# ei2c.net
KiCad netlist of a schematic drawn in EAGLE
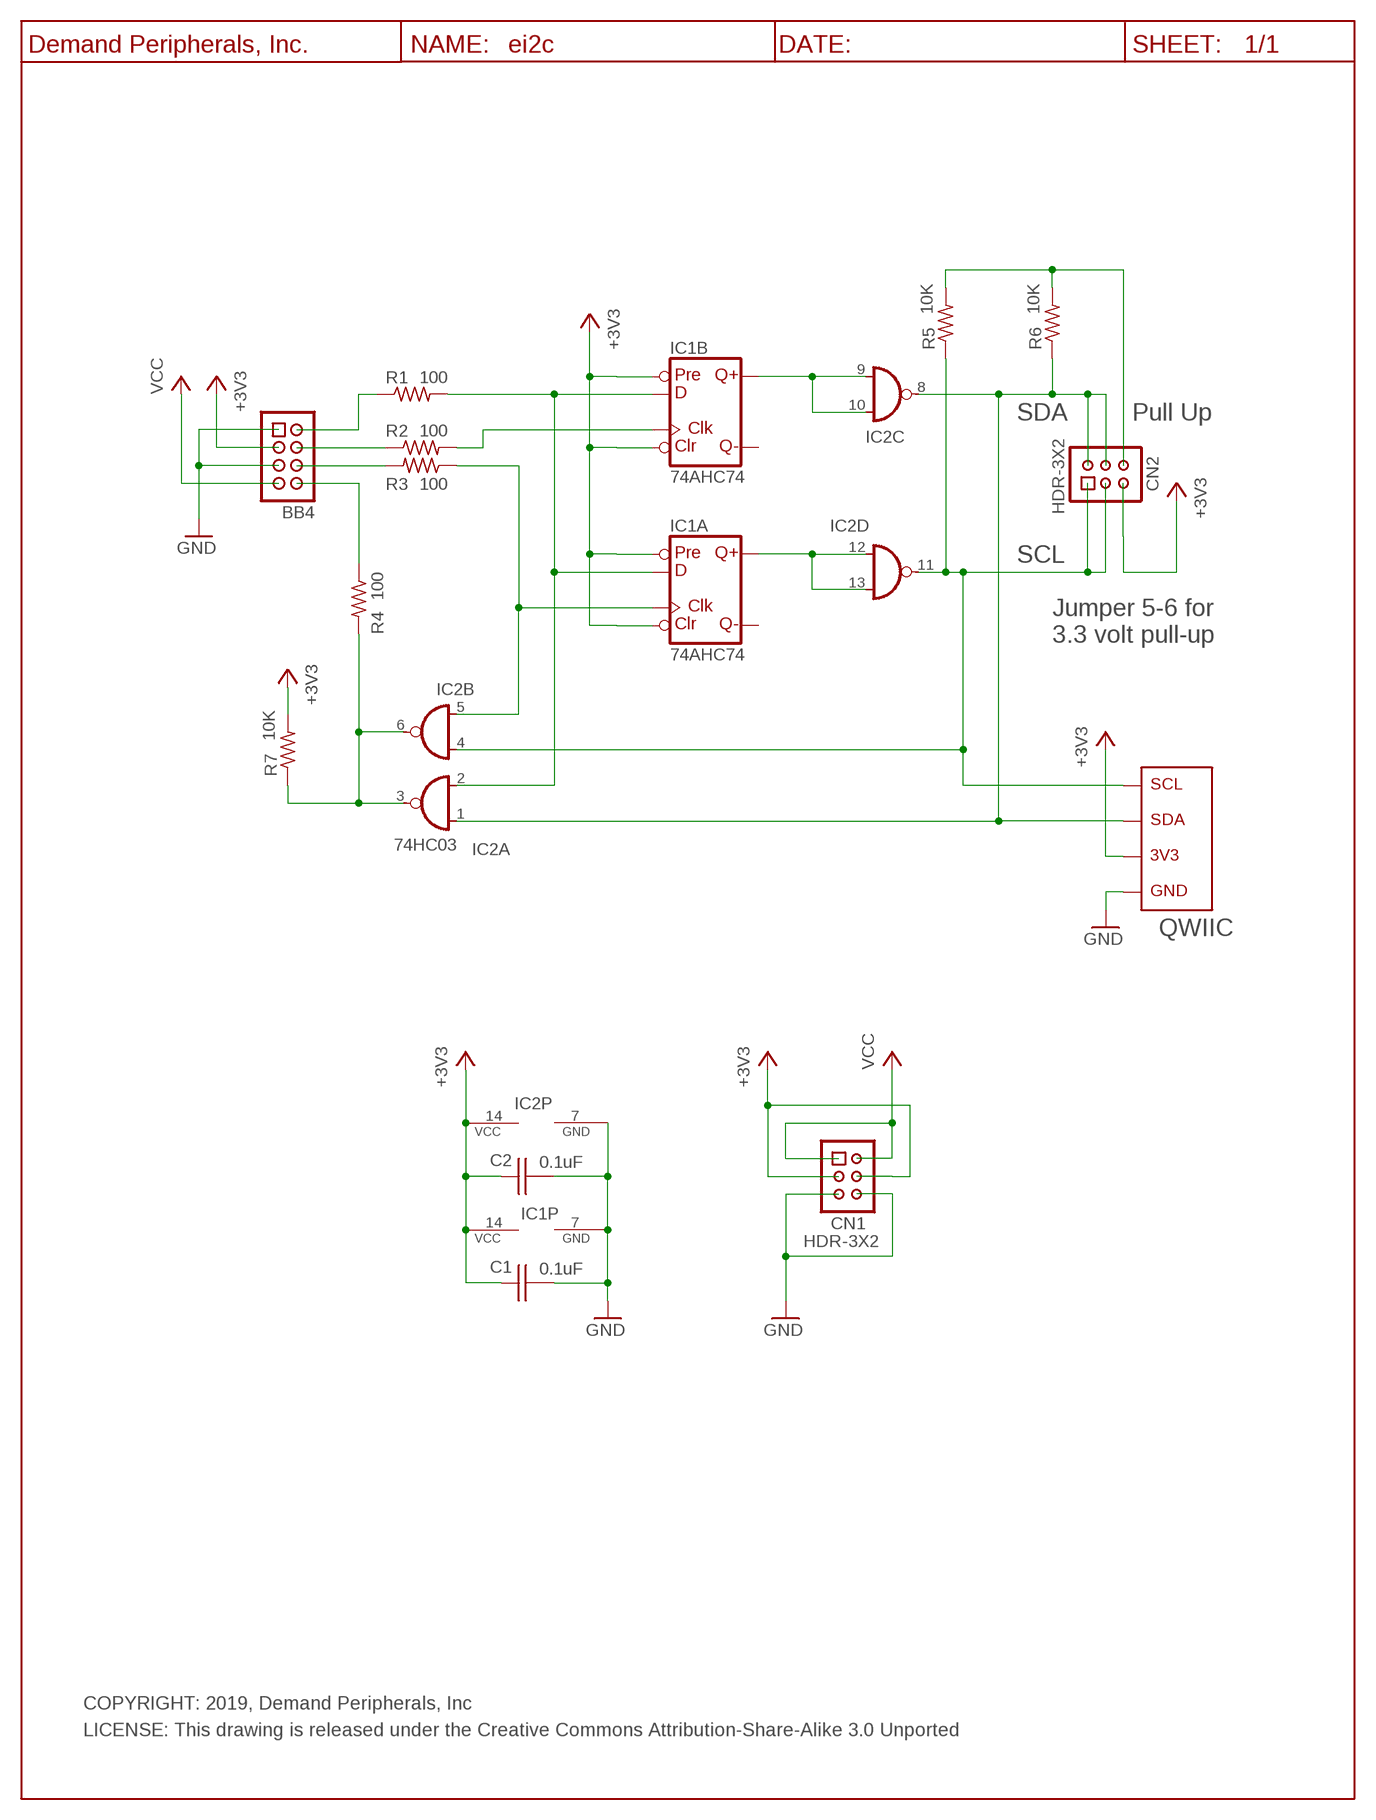
[diagram p0: schematic, sheet 1]

(export (version "E")
  (design (tool "Eeschema 10.0.6"))
  (components
    (comp (ref "BB4")
      (value "BB_CON")
      (footprint "eagle-import:HDR-4X2")
      (libsource (lib "eagle-import") (part "HDR-4X2-SHR"))
    )
    (comp (ref "C1")
      (value "0.1uF")
      (footprint "eagle-import:C0603")
      (libsource (lib "eagle-import") (part "C0.1UF_C0603"))
    )
    (comp (ref "C2")
      (value "0.1uF")
      (footprint "eagle-import:C0603")
      (libsource (lib "eagle-import") (part "C0.1UF_C0603"))
    )
    (comp (ref "CN1")
      (value "HDR-3X2")
      (footprint "eagle-import:HDR-3X2")
      (libsource (lib "eagle-import") (part "HDR-3X2"))
    )
    (comp (ref "CN2")
      (value "HDR-3X2")
      (footprint "eagle-import:HDR-3X2")
      (libsource (lib "eagle-import") (part "HDR-3X2"))
    )
    (comp (ref "IC1")
      (value "74AHC74")
      (footprint "eagle-import:SO14")
      (libsource (lib "eagle-import") (part "74AHC74SS"))
    )
    (comp (ref "IC2")
      (value "74HC03")
      (footprint "eagle-import:SO14")
      (libsource (lib "eagle-import") (part "7403HC"))
    )
    (comp (ref "QWIIC")
      (value "QWIIC-VCN")
      (footprint "eagle-import:QWIIC")
      (libsource (lib "eagle-import") (part "QWIIC-VCN"))
    )
    (comp (ref "R1")
      (value "100")
      (footprint "eagle-import:R0603")
      (libsource (lib "eagle-import") (part "R100_R0603"))
    )
    (comp (ref "R2")
      (value "100")
      (footprint "eagle-import:R0603")
      (libsource (lib "eagle-import") (part "R100_R0603"))
    )
    (comp (ref "R3")
      (value "100")
      (footprint "eagle-import:R0603")
      (libsource (lib "eagle-import") (part "R100_R0603"))
    )
    (comp (ref "R4")
      (value "100")
      (footprint "eagle-import:R0603")
      (libsource (lib "eagle-import") (part "R100_R0603"))
    )
    (comp (ref "R5")
      (value "10K")
      (footprint "eagle-import:R0603")
      (libsource (lib "eagle-import") (part "R10K_R0603"))
    )
    (comp (ref "R6")
      (value "10K")
      (footprint "eagle-import:R0603")
      (libsource (lib "eagle-import") (part "R10K_R0603"))
    )
    (comp (ref "R7")
      (value "10K")
      (footprint "eagle-import:R0603")
      (libsource (lib "eagle-import") (part "R10K_R0603"))
    )
    (comp (ref "U$3")
      (value "DP_FRAME_P")
      (footprint "eagle-import:P_FRAME")
      (libsource (lib "eagle-import") (part "DP_FRAME_P"))
    )
  )
  (nets
    (net (code "1") (name "+3V3") (class "Default")
      (node (ref "BB4") (pin "3") (pinfunction "3_3") (pintype "passive"))
      (node (ref "C1") (pin "1") (pinfunction "1_1") (pintype "passive"))
      (node (ref "C2") (pin "1") (pinfunction "1_1") (pintype "passive"))
      (node (ref "CN1") (pin "3") (pinfunction "3_3") (pintype "passive"))
      (node (ref "CN1") (pin "4") (pinfunction "4_4") (pintype "passive"))
      (node (ref "CN2") (pin "5") (pinfunction "5_5") (pintype "passive"))
      (node (ref "IC1") (pin "1") (pinfunction "CLR_1") (pintype "input"))
      (node (ref "IC1") (pin "10") (pinfunction "PRE_10") (pintype "input"))
      (node (ref "IC1") (pin "13") (pinfunction "CLR_13") (pintype "input"))
      (node (ref "IC1") (pin "14") (pinfunction "VCC_14") (pintype "power_in"))
      (node (ref "IC1") (pin "4") (pinfunction "PRE_4") (pintype "input"))
      (node (ref "IC2") (pin "14") (pinfunction "VCC_14") (pintype "power_in"))
      (node (ref "QWIIC") (pin "2") (pinfunction "2_2") (pintype "passive"))
      (node (ref "R7") (pin "2") (pinfunction "2_2") (pintype "passive"))
    )
    (net (code "2") (name "GND") (class "Default")
      (node (ref "BB4") (pin "1") (pinfunction "1_1") (pintype "passive"))
      (node (ref "BB4") (pin "5") (pinfunction "5_5") (pintype "passive"))
      (node (ref "C1") (pin "2") (pinfunction "2_2") (pintype "passive"))
      (node (ref "C2") (pin "2") (pinfunction "2_2") (pintype "passive"))
      (node (ref "CN1") (pin "5") (pinfunction "5_5") (pintype "passive"))
      (node (ref "CN1") (pin "6") (pinfunction "6_6") (pintype "passive"))
      (node (ref "IC1") (pin "7") (pinfunction "GND_7") (pintype "power_in"))
      (node (ref "IC2") (pin "7") (pinfunction "GND_7") (pintype "power_in"))
      (node (ref "QWIIC") (pin "1") (pinfunction "1_1") (pintype "passive"))
    )
    (net (code "3") (name "Net-(BB4-Pad2)") (class "Default")
      (node (ref "BB4") (pin "2") (pinfunction "2_2") (pintype "passive"))
      (node (ref "R1") (pin "1") (pinfunction "1_1") (pintype "passive"))
    )
    (net (code "4") (name "Net-(BB4-Pad4)") (class "Default")
      (node (ref "BB4") (pin "4") (pinfunction "4_4") (pintype "passive"))
      (node (ref "R2") (pin "1") (pinfunction "1_1") (pintype "passive"))
    )
    (net (code "5") (name "Net-(BB4-Pad6)") (class "Default")
      (node (ref "BB4") (pin "6") (pinfunction "6_6") (pintype "passive"))
      (node (ref "R3") (pin "2") (pinfunction "2_2") (pintype "passive"))
    )
    (net (code "6") (name "Net-(BB4-Pad8)") (class "Default")
      (node (ref "BB4") (pin "8") (pinfunction "8_8") (pintype "passive"))
      (node (ref "R4") (pin "1") (pinfunction "1_1") (pintype "passive"))
    )
    (net (code "7") (name "Net-(CN2-Pad6)") (class "Default")
      (node (ref "CN2") (pin "6") (pinfunction "6_6") (pintype "passive"))
      (node (ref "R5") (pin "2") (pinfunction "2_2") (pintype "passive"))
      (node (ref "R6") (pin "2") (pinfunction "2_2") (pintype "passive"))
    )
    (net (code "8") (name "Net-(IC1A-CLK)") (class "Default")
      (node (ref "IC1") (pin "3") (pinfunction "CLK_3") (pintype "input"))
      (node (ref "IC2") (pin "5") (pinfunction "I1_5") (pintype "input"))
      (node (ref "R3") (pin "1") (pinfunction "1_1") (pintype "passive"))
    )
    (net (code "9") (name "Net-(IC1A-D)") (class "Default")
      (node (ref "IC1") (pin "12") (pinfunction "D_12") (pintype "input"))
      (node (ref "IC1") (pin "2") (pinfunction "D_2") (pintype "input"))
      (node (ref "IC2") (pin "2") (pinfunction "I1_2") (pintype "input"))
      (node (ref "R1") (pin "2") (pinfunction "2_2") (pintype "passive"))
    )
    (net (code "10") (name "Net-(IC1A-Q)") (class "Default")
      (node (ref "IC1") (pin "5") (pinfunction "Q_5") (pintype "output"))
      (node (ref "IC2") (pin "12") (pinfunction "I0_12") (pintype "input"))
      (node (ref "IC2") (pin "13") (pinfunction "I1_13") (pintype "input"))
    )
    (net (code "11") (name "Net-(IC1B-CLK)") (class "Default")
      (node (ref "IC1") (pin "11") (pinfunction "CLK_11") (pintype "input"))
      (node (ref "R2") (pin "2") (pinfunction "2_2") (pintype "passive"))
    )
    (net (code "12") (name "Net-(IC1B-Q)") (class "Default")
      (node (ref "IC1") (pin "9") (pinfunction "Q_9") (pintype "output"))
      (node (ref "IC2") (pin "10") (pinfunction "I1_10") (pintype "input"))
      (node (ref "IC2") (pin "9") (pinfunction "I0_9") (pintype "input"))
    )
    (net (code "13") (name "Net-(IC2A-I0)") (class "Default")
      (node (ref "CN2") (pin "2") (pinfunction "2_2") (pintype "passive"))
      (node (ref "CN2") (pin "4") (pinfunction "4_4") (pintype "passive"))
      (node (ref "IC2") (pin "1") (pinfunction "I0_1") (pintype "input"))
      (node (ref "IC2") (pin "8") (pinfunction "O_8") (pintype "open_collector"))
      (node (ref "QWIIC") (pin "3") (pinfunction "3_3") (pintype "passive"))
      (node (ref "R6") (pin "1") (pinfunction "1_1") (pintype "passive"))
    )
    (net (code "14") (name "Net-(IC2A-O)") (class "Default")
      (node (ref "IC2") (pin "3") (pinfunction "O_3") (pintype "open_collector"))
      (node (ref "IC2") (pin "6") (pinfunction "O_6") (pintype "open_collector"))
      (node (ref "R4") (pin "2") (pinfunction "2_2") (pintype "passive"))
      (node (ref "R7") (pin "1") (pinfunction "1_1") (pintype "passive"))
    )
    (net (code "15") (name "Net-(IC2B-I0)") (class "Default")
      (node (ref "CN2") (pin "1") (pinfunction "1_1") (pintype "passive"))
      (node (ref "CN2") (pin "3") (pinfunction "3_3") (pintype "passive"))
      (node (ref "IC2") (pin "11") (pinfunction "O_11") (pintype "open_collector"))
      (node (ref "IC2") (pin "4") (pinfunction "I0_4") (pintype "input"))
      (node (ref "QWIIC") (pin "4") (pinfunction "4_4") (pintype "passive"))
      (node (ref "R5") (pin "1") (pinfunction "1_1") (pintype "passive"))
    )
    (net (code "16") (name "VCC") (class "Default")
      (node (ref "BB4") (pin "7") (pinfunction "7_7") (pintype "passive"))
      (node (ref "CN1") (pin "1") (pinfunction "1_1") (pintype "passive"))
      (node (ref "CN1") (pin "2") (pinfunction "2_2") (pintype "passive"))
    )
    (net (code "17") (name "unconnected-(IC1A-~{Q}-Pad6)") (class "Default")
      (node (ref "IC1") (pin "6") (pinfunction "~{Q}_6") (pintype "output"))
    )
    (net (code "18") (name "unconnected-(IC1B-~{Q}-Pad8)") (class "Default")
      (node (ref "IC1") (pin "8") (pinfunction "~{Q}_8") (pintype "output"))
    )
  )
)
